# CPU_DDR.net
KiCad netlist of a schematic drawn in Altium Designer
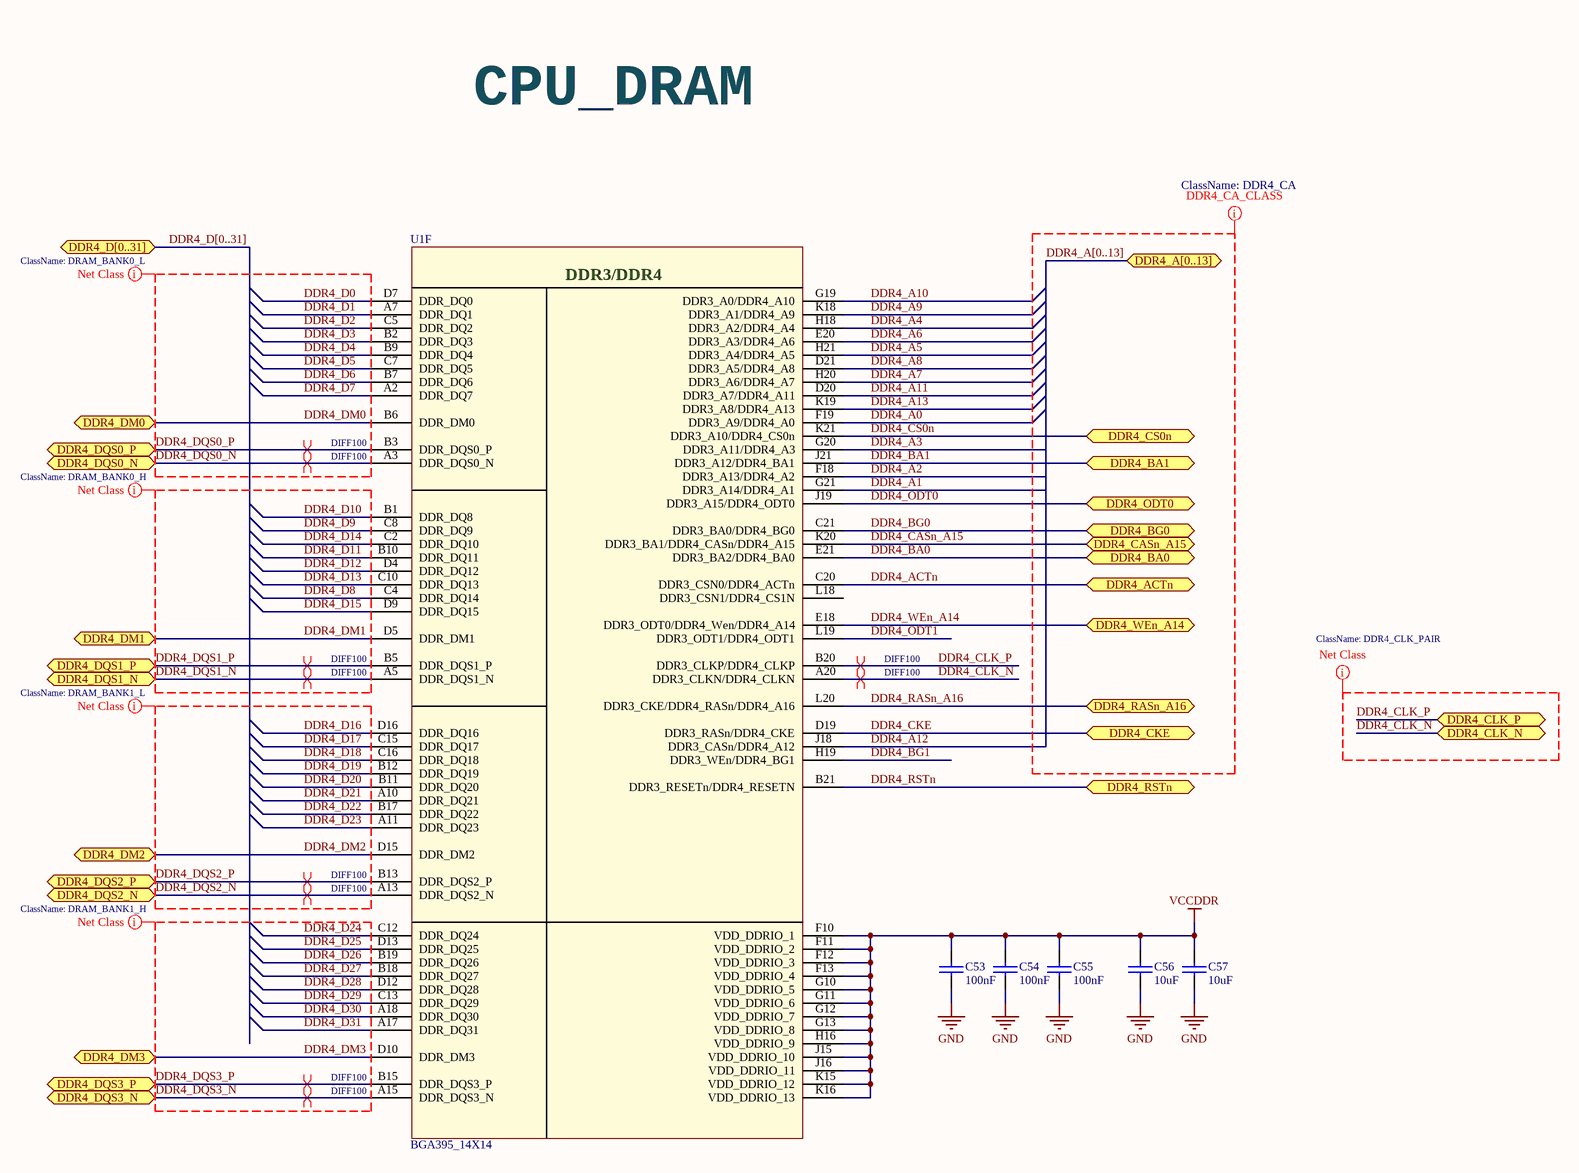
[diagram p0: CPU_DDR.SchDoc]

(export (version "E")
  (design (tool "Eeschema 10.0.6"))
  (components
    (comp (ref "C53")
      (value "100nF")
      (footprint "0402_CC - C")
      (libsource (lib "AAR_RockChip_RK3328") (part "CAP_NP"))
    )
    (comp (ref "C54")
      (value "100nF")
      (footprint "0402_CC - C")
      (libsource (lib "AAR_RockChip_RK3328") (part "CAP_NP"))
    )
    (comp (ref "C55")
      (value "100nF")
      (footprint "0402_CC - C")
      (libsource (lib "AAR_RockChip_RK3328") (part "CAP_NP"))
    )
    (comp (ref "C56")
      (value "10uF")
      (footprint "0603_CC")
      (libsource (lib "AAR_RockChip_RK3328") (part "CAP_NP"))
    )
    (comp (ref "C57")
      (value "10uF")
      (footprint "0603_CC")
      (libsource (lib "AAR_RockChip_RK3328") (part "CAP_NP"))
    )
    (comp (ref "U1")
      (value "BGA395_14X14")
      (footprint "BGA395C65P21X21_1750X1750X117")
      (description "By AAR")
      (libsource (lib "AAR_RockChip_RK3328") (part "RK3328"))
    )
  )
  (nets
    (net (code "1") (name "/DDR4_A0") (class "Default")
      (node (ref "U1") (pin "F19") (pinfunction "DDR3_A9/DDR4_A0_F19") (pintype "passive"))
    )
    (net (code "2") (name "/DDR4_A1") (class "Default")
      (node (ref "U1") (pin "G21") (pinfunction "DDR3_A14/DDR4_A1_G21") (pintype "passive"))
    )
    (net (code "3") (name "/DDR4_A2") (class "Default")
      (node (ref "U1") (pin "F18") (pinfunction "DDR3_A13/DDR4_A2_F18") (pintype "passive"))
    )
    (net (code "4") (name "/DDR4_A3") (class "Default")
      (node (ref "U1") (pin "G20") (pinfunction "DDR3_A11/DDR4_A3_G20") (pintype "passive"))
    )
    (net (code "5") (name "/DDR4_A4") (class "Default")
      (node (ref "U1") (pin "H18") (pinfunction "DDR3_A2/DDR4_A4_H18") (pintype "passive"))
    )
    (net (code "6") (name "/DDR4_A5") (class "Default")
      (node (ref "U1") (pin "H21") (pinfunction "DDR3_A4/DDR4_A5_H21") (pintype "passive"))
    )
    (net (code "7") (name "/DDR4_A6") (class "Default")
      (node (ref "U1") (pin "E20") (pinfunction "DDR3_A3/DDR4_A6_E20") (pintype "passive"))
    )
    (net (code "8") (name "/DDR4_A7") (class "Default")
      (node (ref "U1") (pin "H20") (pinfunction "DDR3_A6/DDR4_A7_H20") (pintype "passive"))
    )
    (net (code "9") (name "/DDR4_A8") (class "Default")
      (node (ref "U1") (pin "D21") (pinfunction "DDR3_A5/DDR4_A8_D21") (pintype "passive"))
    )
    (net (code "10") (name "/DDR4_A9") (class "Default")
      (node (ref "U1") (pin "K18") (pinfunction "DDR3_A1/DDR4_A9_K18") (pintype "passive"))
    )
    (net (code "11") (name "/DDR4_A10") (class "Default")
      (node (ref "U1") (pin "G19") (pinfunction "DDR3_A0/DDR4_A10_G19") (pintype "passive"))
    )
    (net (code "12") (name "/DDR4_A11") (class "Default")
      (node (ref "U1") (pin "D20") (pinfunction "DDR3_A7/DDR4_A11_D20") (pintype "passive"))
    )
    (net (code "13") (name "/DDR4_A12") (class "Default")
      (node (ref "U1") (pin "J18") (pinfunction "DDR3_CASn/DDR4_A12_J18") (pintype "passive"))
    )
    (net (code "14") (name "/DDR4_A13") (class "Default")
      (node (ref "U1") (pin "K19") (pinfunction "DDR3_A8/DDR4_A13_K19") (pintype "passive"))
    )
    (net (code "15") (name "/DDR4_ACTn") (class "Default")
      (node (ref "U1") (pin "C20") (pinfunction "DDR3_CSN0/DDR4_ACTn_C20") (pintype "passive"))
    )
    (net (code "17") (name "/DDR4_BA0") (class "Default")
      (node (ref "U1") (pin "E21") (pinfunction "DDR3_BA2/DDR4_BA0_E21") (pintype "passive"))
    )
    (net (code "18") (name "/DDR4_BA1") (class "Default")
      (node (ref "U1") (pin "J21") (pinfunction "DDR3_A12/DDR4_BA1_J21") (pintype "passive"))
    )
    (net (code "19") (name "/DDR4_BG0") (class "Default")
      (node (ref "U1") (pin "C21") (pinfunction "DDR3_BA0/DDR4_BG0_C21") (pintype "passive"))
    )
    (net (code "20") (name "/DDR4_BG1") (class "Default")
      (node (ref "U1") (pin "H19") (pinfunction "DDR3_WEn/DDR4_BG1_H19") (pintype "passive"))
    )
    (net (code "21") (name "/DDR4_CASn_A15") (class "Default")
      (node (ref "U1") (pin "K20") (pinfunction "DDR3_BA1/DDR4_CASn/DDR4_A15_K20") (pintype "passive"))
    )
    (net (code "22") (name "/DDR4_CKE") (class "Default")
      (node (ref "U1") (pin "D19") (pinfunction "DDR3_RASn/DDR4_CKE_D19") (pintype "passive"))
    )
    (net (code "23") (name "/DDR4_CLK_N") (class "Default")
      (node (ref "U1") (pin "A20") (pinfunction "DDR3_CLKN/DDR4_CLKN_A20") (pintype "passive"))
    )
    (net (code "24") (name "/DDR4_CLK_P") (class "Default")
      (node (ref "U1") (pin "B20") (pinfunction "DDR3_CLKP/DDR4_CLKP_B20") (pintype "passive"))
    )
    (net (code "25") (name "/DDR4_CS0n") (class "Default")
      (node (ref "U1") (pin "K21") (pinfunction "DDR3_A10/DDR4_CS0n_K21") (pintype "passive"))
    )
    (net (code "26") (name "/DDR4_D0") (class "Default")
      (node (ref "U1") (pin "D7") (pinfunction "DDR_DQ0_D7") (pintype "passive"))
    )
    (net (code "27") (name "/DDR4_D1") (class "Default")
      (node (ref "U1") (pin "A7") (pinfunction "DDR_DQ1_A7") (pintype "passive"))
    )
    (net (code "28") (name "/DDR4_D2") (class "Default")
      (node (ref "U1") (pin "C5") (pinfunction "DDR_DQ2_C5") (pintype "passive"))
    )
    (net (code "29") (name "/DDR4_D3") (class "Default")
      (node (ref "U1") (pin "B2") (pinfunction "DDR_DQ3_B2") (pintype "passive"))
    )
    (net (code "30") (name "/DDR4_D4") (class "Default")
      (node (ref "U1") (pin "B9") (pinfunction "DDR_DQ4_B9") (pintype "passive"))
    )
    (net (code "31") (name "/DDR4_D5") (class "Default")
      (node (ref "U1") (pin "C7") (pinfunction "DDR_DQ5_C7") (pintype "passive"))
    )
    (net (code "32") (name "/DDR4_D6") (class "Default")
      (node (ref "U1") (pin "B7") (pinfunction "DDR_DQ6_B7") (pintype "passive"))
    )
    (net (code "33") (name "/DDR4_D7") (class "Default")
      (node (ref "U1") (pin "A2") (pinfunction "DDR_DQ7_A2") (pintype "passive"))
    )
    (net (code "34") (name "/DDR4_D8") (class "Default")
      (node (ref "U1") (pin "C4") (pinfunction "DDR_DQ14_C4") (pintype "passive"))
    )
    (net (code "35") (name "/DDR4_D9") (class "Default")
      (node (ref "U1") (pin "C8") (pinfunction "DDR_DQ9_C8") (pintype "passive"))
    )
    (net (code "36") (name "/DDR4_D10") (class "Default")
      (node (ref "U1") (pin "B1") (pinfunction "DDR_DQ8_B1") (pintype "passive"))
    )
    (net (code "37") (name "/DDR4_D11") (class "Default")
      (node (ref "U1") (pin "B10") (pinfunction "DDR_DQ11_B10") (pintype "passive"))
    )
    (net (code "38") (name "/DDR4_D12") (class "Default")
      (node (ref "U1") (pin "D4") (pinfunction "DDR_DQ12_D4") (pintype "passive"))
    )
    (net (code "39") (name "/DDR4_D13") (class "Default")
      (node (ref "U1") (pin "C10") (pinfunction "DDR_DQ13_C10") (pintype "passive"))
    )
    (net (code "40") (name "/DDR4_D14") (class "Default")
      (node (ref "U1") (pin "C2") (pinfunction "DDR_DQ10_C2") (pintype "passive"))
    )
    (net (code "41") (name "/DDR4_D15") (class "Default")
      (node (ref "U1") (pin "D9") (pinfunction "DDR_DQ15_D9") (pintype "passive"))
    )
    (net (code "42") (name "/DDR4_D16") (class "Default")
      (node (ref "U1") (pin "D16") (pinfunction "DDR_DQ16_D16") (pintype "passive"))
    )
    (net (code "43") (name "/DDR4_D17") (class "Default")
      (node (ref "U1") (pin "C15") (pinfunction "DDR_DQ17_C15") (pintype "passive"))
    )
    (net (code "44") (name "/DDR4_D18") (class "Default")
      (node (ref "U1") (pin "C16") (pinfunction "DDR_DQ18_C16") (pintype "passive"))
    )
    (net (code "45") (name "/DDR4_D19") (class "Default")
      (node (ref "U1") (pin "B12") (pinfunction "DDR_DQ19_B12") (pintype "passive"))
    )
    (net (code "46") (name "/DDR4_D20") (class "Default")
      (node (ref "U1") (pin "B11") (pinfunction "DDR_DQ20_B11") (pintype "passive"))
    )
    (net (code "47") (name "/DDR4_D21") (class "Default")
      (node (ref "U1") (pin "A10") (pinfunction "DDR_DQ21_A10") (pintype "passive"))
    )
    (net (code "48") (name "/DDR4_D22") (class "Default")
      (node (ref "U1") (pin "B17") (pinfunction "DDR_DQ22_B17") (pintype "passive"))
    )
    (net (code "49") (name "/DDR4_D23") (class "Default")
      (node (ref "U1") (pin "A11") (pinfunction "DDR_DQ23_A11") (pintype "passive"))
    )
    (net (code "50") (name "/DDR4_D24") (class "Default")
      (node (ref "U1") (pin "C12") (pinfunction "DDR_DQ24_C12") (pintype "passive"))
    )
    (net (code "51") (name "/DDR4_D25") (class "Default")
      (node (ref "U1") (pin "D13") (pinfunction "DDR_DQ25_D13") (pintype "passive"))
    )
    (net (code "52") (name "/DDR4_D26") (class "Default")
      (node (ref "U1") (pin "B19") (pinfunction "DDR_DQ26_B19") (pintype "passive"))
    )
    (net (code "53") (name "/DDR4_D27") (class "Default")
      (node (ref "U1") (pin "B18") (pinfunction "DDR_DQ27_B18") (pintype "passive"))
    )
    (net (code "54") (name "/DDR4_D28") (class "Default")
      (node (ref "U1") (pin "D12") (pinfunction "DDR_DQ28_D12") (pintype "passive"))
    )
    (net (code "55") (name "/DDR4_D29") (class "Default")
      (node (ref "U1") (pin "C13") (pinfunction "DDR_DQ29_C13") (pintype "passive"))
    )
    (net (code "56") (name "/DDR4_D30") (class "Default")
      (node (ref "U1") (pin "A18") (pinfunction "DDR_DQ30_A18") (pintype "passive"))
    )
    (net (code "57") (name "/DDR4_D31") (class "Default")
      (node (ref "U1") (pin "A17") (pinfunction "DDR_DQ31_A17") (pintype "passive"))
    )
    (net (code "58") (name "/DDR4_DM0") (class "Default")
      (node (ref "U1") (pin "B6") (pinfunction "DDR_DM0_B6") (pintype "passive"))
    )
    (net (code "59") (name "/DDR4_DM1") (class "Default")
      (node (ref "U1") (pin "D5") (pinfunction "DDR_DM1_D5") (pintype "passive"))
    )
    (net (code "60") (name "/DDR4_DM2") (class "Default")
      (node (ref "U1") (pin "D15") (pinfunction "DDR_DM2_D15") (pintype "passive"))
    )
    (net (code "61") (name "/DDR4_DM3") (class "Default")
      (node (ref "U1") (pin "D10") (pinfunction "DDR_DM3_D10") (pintype "passive"))
    )
    (net (code "62") (name "/DDR4_DQS0_N") (class "Default")
      (node (ref "U1") (pin "A3") (pinfunction "DDR_DQS0_N_A3") (pintype "passive"))
    )
    (net (code "63") (name "/DDR4_DQS0_P") (class "Default")
      (node (ref "U1") (pin "B3") (pinfunction "DDR_DQS0_P_B3") (pintype "passive"))
    )
    (net (code "64") (name "/DDR4_DQS1_N") (class "Default")
      (node (ref "U1") (pin "A5") (pinfunction "DDR_DQS1_N_A5") (pintype "passive"))
    )
    (net (code "65") (name "/DDR4_DQS1_P") (class "Default")
      (node (ref "U1") (pin "B5") (pinfunction "DDR_DQS1_P_B5") (pintype "passive"))
    )
    (net (code "66") (name "/DDR4_DQS2_N") (class "Default")
      (node (ref "U1") (pin "A13") (pinfunction "DDR_DQS2_N_A13") (pintype "passive"))
    )
    (net (code "67") (name "/DDR4_DQS2_P") (class "Default")
      (node (ref "U1") (pin "B13") (pinfunction "DDR_DQS2_P_B13") (pintype "passive"))
    )
    (net (code "68") (name "/DDR4_DQS3_N") (class "Default")
      (node (ref "U1") (pin "A15") (pinfunction "DDR_DQS3_N_A15") (pintype "passive"))
    )
    (net (code "69") (name "/DDR4_DQS3_P") (class "Default")
      (node (ref "U1") (pin "B15") (pinfunction "DDR_DQS3_P_B15") (pintype "passive"))
    )
    (net (code "71") (name "/DDR4_ODT0") (class "Default")
      (node (ref "U1") (pin "J19") (pinfunction "DDR3_A15/DDR4_ODT0_J19") (pintype "passive"))
    )
    (net (code "72") (name "/DDR4_ODT1") (class "Default")
      (node (ref "U1") (pin "L19") (pinfunction "DDR3_ODT1/DDR4_ODT1_L19") (pintype "passive"))
    )
    (net (code "73") (name "/DDR4_RASn_A16") (class "Default")
      (node (ref "U1") (pin "L20") (pinfunction "DDR3_CKE/DDR4_RASn/DDR4_A16_L20") (pintype "passive"))
    )
    (net (code "74") (name "/DDR4_RSTn") (class "Default")
      (node (ref "U1") (pin "B21") (pinfunction "DDR3_RESETn/DDR4_RESETN_B21") (pintype "passive"))
    )
    (net (code "75") (name "/DDR4_WEn_A14") (class "Default")
      (node (ref "U1") (pin "E18") (pinfunction "DDR3_ODT0/DDR4_Wen/DDR4_A14_E18") (pintype "passive"))
    )
    (net (code "76") (name "GND") (class "Default")
      (node (ref "C53") (pin "2") (pinfunction "2_2") (pintype "passive"))
      (node (ref "C54") (pin "2") (pinfunction "2_2") (pintype "passive"))
      (node (ref "C55") (pin "2") (pinfunction "2_2") (pintype "passive"))
      (node (ref "C56") (pin "2") (pinfunction "2_2") (pintype "passive"))
      (node (ref "C57") (pin "2") (pinfunction "2_2") (pintype "passive"))
    )
    (net (code "77") (name "VCCDDR") (class "Default")
      (node (ref "C53") (pin "1") (pinfunction "1_1") (pintype "passive"))
      (node (ref "C54") (pin "1") (pinfunction "1_1") (pintype "passive"))
      (node (ref "C55") (pin "1") (pinfunction "1_1") (pintype "passive"))
      (node (ref "C56") (pin "1") (pinfunction "1_1") (pintype "passive"))
      (node (ref "C57") (pin "1") (pinfunction "1_1") (pintype "passive"))
      (node (ref "U1") (pin "F10") (pinfunction "VDD_DDRIO_1_F10") (pintype "passive"))
      (node (ref "U1") (pin "F11") (pinfunction "VDD_DDRIO_2_F11") (pintype "passive"))
      (node (ref "U1") (pin "F12") (pinfunction "VDD_DDRIO_3_F12") (pintype "passive"))
      (node (ref "U1") (pin "F13") (pinfunction "VDD_DDRIO_4_F13") (pintype "passive"))
      (node (ref "U1") (pin "G10") (pinfunction "VDD_DDRIO_5_G10") (pintype "passive"))
      (node (ref "U1") (pin "G11") (pinfunction "VDD_DDRIO_6_G11") (pintype "passive"))
      (node (ref "U1") (pin "G12") (pinfunction "VDD_DDRIO_7_G12") (pintype "passive"))
      (node (ref "U1") (pin "G13") (pinfunction "VDD_DDRIO_8_G13") (pintype "passive"))
      (node (ref "U1") (pin "H16") (pinfunction "VDD_DDRIO_9_H16") (pintype "passive"))
      (node (ref "U1") (pin "J15") (pinfunction "VDD_DDRIO_10_J15") (pintype "passive"))
      (node (ref "U1") (pin "J16") (pinfunction "VDD_DDRIO_11_J16") (pintype "passive"))
      (node (ref "U1") (pin "K15") (pinfunction "VDD_DDRIO_12_K15") (pintype "passive"))
      (node (ref "U1") (pin "K16") (pinfunction "VDD_DDRIO_13_K16") (pintype "passive"))
    )
    (net (code "78") (name "unconnected-(U1F-DDR3_CSN1{slash}DDR4_CS1N-PadL18)") (class "Default")
      (node (ref "U1") (pin "L18") (pinfunction "DDR3_CSN1/DDR4_CS1N_L18") (pintype "passive"))
    )
  )
)
